# STM32_MPU_IOs.net
KiCad netlist of a schematic drawn in Altium Designer
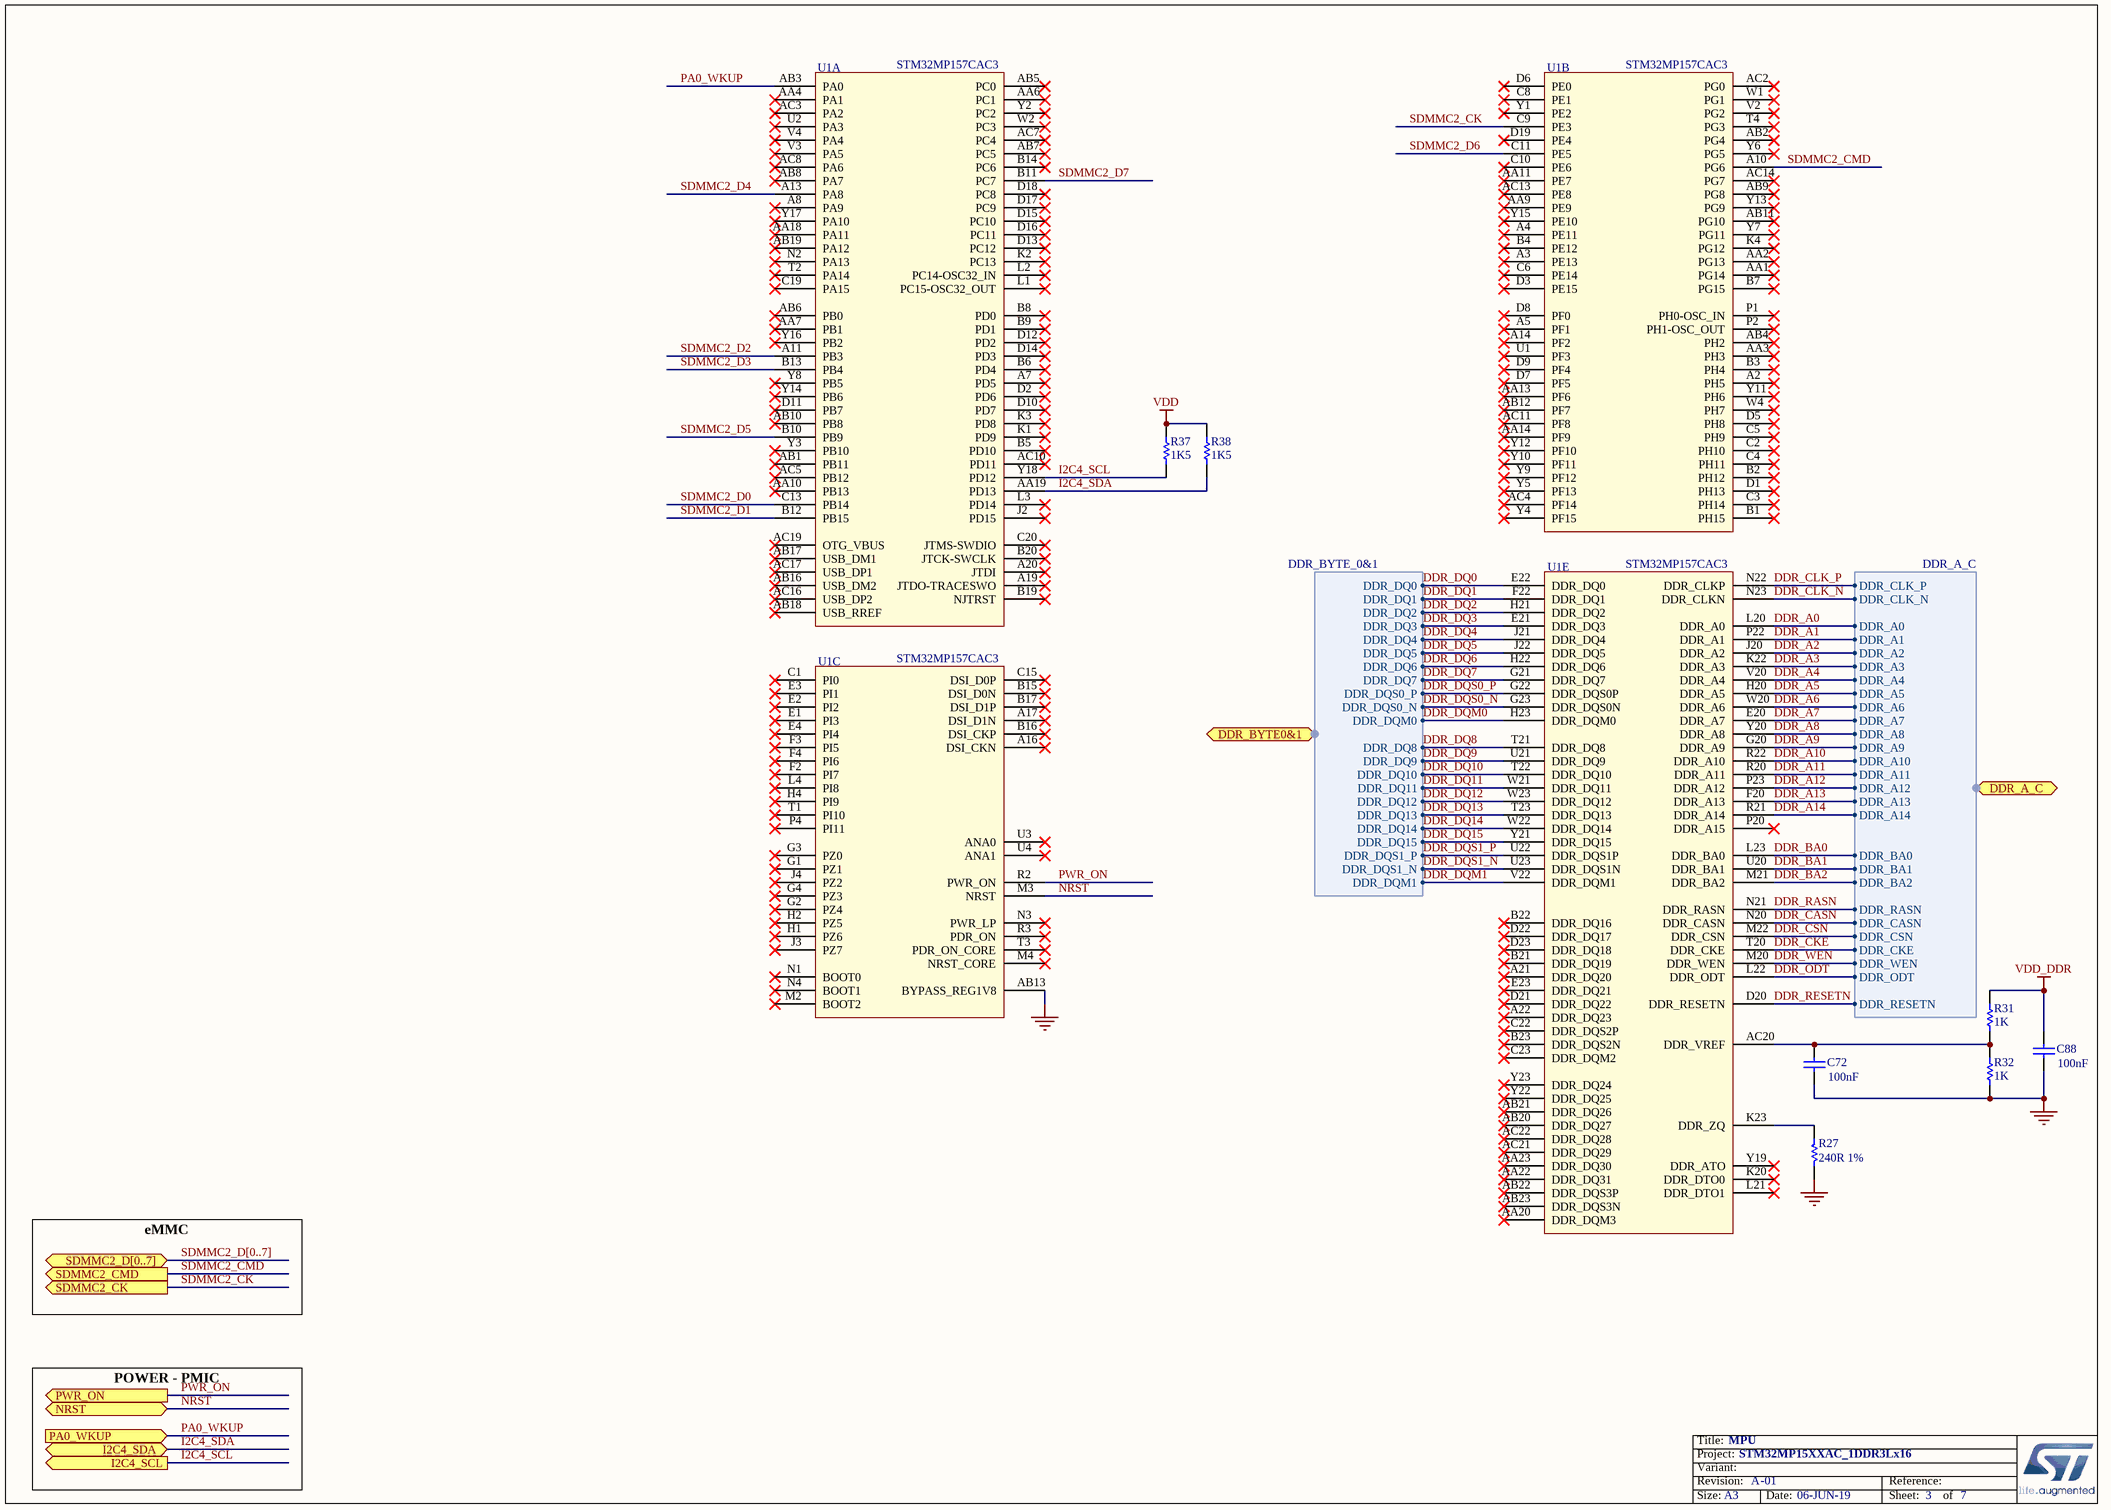
[diagram p0: STM32_MPU_IOs.SchDoc]

(export (version "E")
  (design (tool "Eeschema 10.0.6"))
  (components
    (comp (ref "C72")
      (value "100nF")
      (footprint "C0402")
      (description "Capacitor, MLCC, 100nF, 16V, X7R, 10%, 0402, T=0.5mm")
      (fields
        (field (name "INTERNAL_PART_NUMBER") "MCD-00006")
        (field (name "MANUFACTURER_PART_NUMBER") "CC0402KRX7R7BB104")
        (field (name "PROVIDED_BY") "SUBCO")
      )
      (libsource (lib "MCD_PARTS_database") (part "Capacitor"))
    )
    (comp (ref "C88")
      (value "100nF")
      (footprint "C0402")
      (description "Capacitor, MLCC, 100nF, 16V, X7R, 10%, 0402, T=0.5mm")
      (fields
        (field (name "INTERNAL_PART_NUMBER") "MCD-00006")
        (field (name "MANUFACTURER_PART_NUMBER") "CC0402KRX7R7BB104")
        (field (name "PROVIDED_BY") "SUBCO")
      )
      (libsource (lib "MCD_PARTS_database") (part "Capacitor"))
    )
    (comp (ref "R27")
      (value "240R 1%")
      (footprint "R0402")
      (description "Resistor,240R,0402,1%,1/16W")
      (fields
        (field (name "INTERNAL_PART_NUMBER") "MCD-00120")
        (field (name "MANUFACTURER_PART_NUMBER") "RC0402FR-07240RL")
        (field (name "PROVIDED_BY") "SUBCO")
      )
      (libsource (lib "MCD_PARTS_database") (part "Resistor"))
    )
    (comp (ref "R31")
      (value "1K")
      (footprint "R0402")
      (description "Resistor,1K,0402,1%,1/16W")
      (fields
        (field (name "INTERNAL_PART_NUMBER") "MCD-00061")
        (field (name "MANUFACTURER_PART_NUMBER") "RC0402FR-071KL")
        (field (name "PROVIDED_BY") "SUBCO")
      )
      (libsource (lib "MCD_PARTS_database") (part "Resistor"))
    )
    (comp (ref "R32")
      (value "1K")
      (footprint "R0402")
      (description "Resistor,1K,0402,1%,1/16W")
      (fields
        (field (name "INTERNAL_PART_NUMBER") "MCD-00061")
        (field (name "MANUFACTURER_PART_NUMBER") "RC0402FR-071KL")
        (field (name "PROVIDED_BY") "SUBCO")
      )
      (libsource (lib "MCD_PARTS_database") (part "Resistor"))
    )
    (comp (ref "R37")
      (value "1K5")
      (footprint "R0402")
      (description "Resistor,1K5,0402,1%,1/16W")
      (fields
        (field (name "INTERNAL_PART_NUMBER") "MCD-00068")
        (field (name "MANUFACTURER_PART_NUMBER") "RC0402FR-071K5L")
        (field (name "PROVIDED_BY") "SUBCO")
      )
      (libsource (lib "MCD_PARTS_database") (part "Resistor"))
    )
    (comp (ref "R38")
      (value "1K5")
      (footprint "R0402")
      (description "Resistor,1K5,0402,1%,1/16W")
      (fields
        (field (name "INTERNAL_PART_NUMBER") "MCD-00068")
        (field (name "MANUFACTURER_PART_NUMBER") "RC0402FR-071K5L")
        (field (name "PROVIDED_BY") "SUBCO")
      )
      (libsource (lib "MCD_PARTS_database") (part "Resistor"))
    )
    (comp (ref "U1")
      (value "STM32MP157CAC3")
      (footprint "ICC_TFBGA361_12X12_STM32MP157CAC3_P050-065")
      (description "MPU TFBGA12x12 secure boot+crypto")
      (fields
        (field (name "INTERNAL_PART_NUMBER") "MCD-00677")
        (field (name "MANUFACTURER") "STMICROELECTRONICS")
        (field (name "PROVIDED_BY") "SUBCO with ST control")
      )
      (libsource (lib "MCD_PARTS_database") (part "STM32MP157CAC3"))
    )
  )
  (nets
    (net (code "3") (name "/DDR_A0") (class "Default")
      (node (ref "U1") (pin "L20") (pinfunction "DDR_A0_L20") (pintype "passive"))
    )
    (net (code "4") (name "/DDR_A1") (class "Default")
      (node (ref "U1") (pin "P22") (pinfunction "DDR_A1_P22") (pintype "passive"))
    )
    (net (code "5") (name "/DDR_A2") (class "Default")
      (node (ref "U1") (pin "J20") (pinfunction "DDR_A2_J20") (pintype "passive"))
    )
    (net (code "6") (name "/DDR_A3") (class "Default")
      (node (ref "U1") (pin "K22") (pinfunction "DDR_A3_K22") (pintype "passive"))
    )
    (net (code "7") (name "/DDR_A4") (class "Default")
      (node (ref "U1") (pin "V20") (pinfunction "DDR_A4_V20") (pintype "passive"))
    )
    (net (code "8") (name "/DDR_A5") (class "Default")
      (node (ref "U1") (pin "H20") (pinfunction "DDR_A5_H20") (pintype "passive"))
    )
    (net (code "9") (name "/DDR_A6") (class "Default")
      (node (ref "U1") (pin "W20") (pinfunction "DDR_A6_W20") (pintype "passive"))
    )
    (net (code "10") (name "/DDR_A7") (class "Default")
      (node (ref "U1") (pin "E20") (pinfunction "DDR_A7_E20") (pintype "passive"))
    )
    (net (code "11") (name "/DDR_A8") (class "Default")
      (node (ref "U1") (pin "Y20") (pinfunction "DDR_A8_Y20") (pintype "passive"))
    )
    (net (code "12") (name "/DDR_A9") (class "Default")
      (node (ref "U1") (pin "G20") (pinfunction "DDR_A9_G20") (pintype "passive"))
    )
    (net (code "13") (name "/DDR_A10") (class "Default")
      (node (ref "U1") (pin "R22") (pinfunction "DDR_A10_R22") (pintype "passive"))
    )
    (net (code "14") (name "/DDR_A11") (class "Default")
      (node (ref "U1") (pin "R20") (pinfunction "DDR_A11_R20") (pintype "passive"))
    )
    (net (code "15") (name "/DDR_A12") (class "Default")
      (node (ref "U1") (pin "P23") (pinfunction "DDR_A12_P23") (pintype "passive"))
    )
    (net (code "16") (name "/DDR_A13") (class "Default")
      (node (ref "U1") (pin "F20") (pinfunction "DDR_A13_F20") (pintype "passive"))
    )
    (net (code "17") (name "/DDR_A14") (class "Default")
      (node (ref "U1") (pin "R21") (pinfunction "DDR_A14_R21") (pintype "passive"))
    )
    (net (code "18") (name "/DDR_BA0") (class "Default")
      (node (ref "U1") (pin "L23") (pinfunction "DDR_BA0_L23") (pintype "passive"))
    )
    (net (code "19") (name "/DDR_BA1") (class "Default")
      (node (ref "U1") (pin "U20") (pinfunction "DDR_BA1_U20") (pintype "passive"))
    )
    (net (code "20") (name "/DDR_BA2") (class "Default")
      (node (ref "U1") (pin "M21") (pinfunction "DDR_BA2_M21") (pintype "passive"))
    )
    (net (code "21") (name "/DDR_CASN") (class "Default")
      (node (ref "U1") (pin "N20") (pinfunction "DDR_CASN_N20") (pintype "passive"))
    )
    (net (code "22") (name "/DDR_CKE") (class "Default")
      (node (ref "U1") (pin "T20") (pinfunction "DDR_CKE_T20") (pintype "passive"))
    )
    (net (code "23") (name "/DDR_CLK_N") (class "Default")
      (node (ref "U1") (pin "N23") (pinfunction "DDR_CLKN_N23") (pintype "passive"))
    )
    (net (code "24") (name "/DDR_CLK_P") (class "Default")
      (node (ref "U1") (pin "N22") (pinfunction "DDR_CLKP_N22") (pintype "passive"))
    )
    (net (code "25") (name "/DDR_CSN") (class "Default")
      (node (ref "U1") (pin "M22") (pinfunction "DDR_CSN_M22") (pintype "passive"))
    )
    (net (code "26") (name "/DDR_DQ0") (class "Default")
      (node (ref "U1") (pin "E22") (pinfunction "DDR_DQ0_E22") (pintype "passive"))
    )
    (net (code "27") (name "/DDR_DQ1") (class "Default")
      (node (ref "U1") (pin "F22") (pinfunction "DDR_DQ1_F22") (pintype "passive"))
    )
    (net (code "28") (name "/DDR_DQ2") (class "Default")
      (node (ref "U1") (pin "H21") (pinfunction "DDR_DQ2_H21") (pintype "passive"))
    )
    (net (code "29") (name "/DDR_DQ3") (class "Default")
      (node (ref "U1") (pin "E21") (pinfunction "DDR_DQ3_E21") (pintype "passive"))
    )
    (net (code "30") (name "/DDR_DQ4") (class "Default")
      (node (ref "U1") (pin "J21") (pinfunction "DDR_DQ4_J21") (pintype "passive"))
    )
    (net (code "31") (name "/DDR_DQ5") (class "Default")
      (node (ref "U1") (pin "J22") (pinfunction "DDR_DQ5_J22") (pintype "passive"))
    )
    (net (code "32") (name "/DDR_DQ6") (class "Default")
      (node (ref "U1") (pin "H22") (pinfunction "DDR_DQ6_H22") (pintype "passive"))
    )
    (net (code "33") (name "/DDR_DQ7") (class "Default")
      (node (ref "U1") (pin "G21") (pinfunction "DDR_DQ7_G21") (pintype "passive"))
    )
    (net (code "34") (name "/DDR_DQ8") (class "Default")
      (node (ref "U1") (pin "T21") (pinfunction "DDR_DQ8_T21") (pintype "passive"))
    )
    (net (code "35") (name "/DDR_DQ9") (class "Default")
      (node (ref "U1") (pin "U21") (pinfunction "DDR_DQ9_U21") (pintype "passive"))
    )
    (net (code "36") (name "/DDR_DQ10") (class "Default")
      (node (ref "U1") (pin "T22") (pinfunction "DDR_DQ10_T22") (pintype "passive"))
    )
    (net (code "37") (name "/DDR_DQ11") (class "Default")
      (node (ref "U1") (pin "W21") (pinfunction "DDR_DQ11_W21") (pintype "passive"))
    )
    (net (code "38") (name "/DDR_DQ12") (class "Default")
      (node (ref "U1") (pin "W23") (pinfunction "DDR_DQ12_W23") (pintype "passive"))
    )
    (net (code "39") (name "/DDR_DQ13") (class "Default")
      (node (ref "U1") (pin "T23") (pinfunction "DDR_DQ13_T23") (pintype "passive"))
    )
    (net (code "40") (name "/DDR_DQ14") (class "Default")
      (node (ref "U1") (pin "W22") (pinfunction "DDR_DQ14_W22") (pintype "passive"))
    )
    (net (code "41") (name "/DDR_DQ15") (class "Default")
      (node (ref "U1") (pin "Y21") (pinfunction "DDR_DQ15_Y21") (pintype "passive"))
    )
    (net (code "42") (name "/DDR_DQM0") (class "Default")
      (node (ref "U1") (pin "H23") (pinfunction "DDR_DQM0_H23") (pintype "passive"))
    )
    (net (code "43") (name "/DDR_DQM1") (class "Default")
      (node (ref "U1") (pin "V22") (pinfunction "DDR_DQM1_V22") (pintype "passive"))
    )
    (net (code "44") (name "/DDR_DQS0_N") (class "Default")
      (node (ref "U1") (pin "G23") (pinfunction "DDR_DQS0N_G23") (pintype "passive"))
    )
    (net (code "45") (name "/DDR_DQS0_P") (class "Default")
      (node (ref "U1") (pin "G22") (pinfunction "DDR_DQS0P_G22") (pintype "passive"))
    )
    (net (code "46") (name "/DDR_DQS1_N") (class "Default")
      (node (ref "U1") (pin "U23") (pinfunction "DDR_DQS1N_U23") (pintype "passive"))
    )
    (net (code "47") (name "/DDR_DQS1_P") (class "Default")
      (node (ref "U1") (pin "U22") (pinfunction "DDR_DQS1P_U22") (pintype "passive"))
    )
    (net (code "48") (name "/DDR_ODT") (class "Default")
      (node (ref "U1") (pin "L22") (pinfunction "DDR_ODT_L22") (pintype "passive"))
    )
    (net (code "49") (name "/DDR_RASN") (class "Default")
      (node (ref "U1") (pin "N21") (pinfunction "DDR_RASN_N21") (pintype "passive"))
    )
    (net (code "50") (name "/DDR_RESETN") (class "Default")
      (node (ref "U1") (pin "D20") (pinfunction "DDR_RESETN_D20") (pintype "passive"))
    )
    (net (code "51") (name "/DDR_WEN") (class "Default")
      (node (ref "U1") (pin "M20") (pinfunction "DDR_WEN_M20") (pintype "passive"))
    )
    (net (code "52") (name "/I2C4_SCL") (class "Default")
      (node (ref "R37") (pin "2") (pinfunction "2_2") (pintype "passive"))
      (node (ref "U1") (pin "Y18") (pinfunction "PD12_Y18") (pintype "passive"))
    )
    (net (code "53") (name "/I2C4_SDA") (class "Default")
      (node (ref "R38") (pin "2") (pinfunction "2_2") (pintype "passive"))
      (node (ref "U1") (pin "AA19") (pinfunction "PD13_AA19") (pintype "passive"))
    )
    (net (code "54") (name "/NRST") (class "Default")
      (node (ref "U1") (pin "M3") (pinfunction "NRST_M3") (pintype "passive"))
    )
    (net (code "55") (name "/PA0_WKUP") (class "Default")
      (node (ref "U1") (pin "AB3") (pinfunction "PA0_AB3") (pintype "passive"))
    )
    (net (code "56") (name "/PWR_ON") (class "Default")
      (node (ref "U1") (pin "R2") (pinfunction "PWR_ON_R2") (pintype "passive"))
    )
    (net (code "57") (name "/SDMMC2_CK") (class "Default")
      (node (ref "U1") (pin "C9") (pinfunction "PE3_C9") (pintype "passive"))
    )
    (net (code "58") (name "/SDMMC2_CMD") (class "Default")
      (node (ref "U1") (pin "A10") (pinfunction "PG6_A10") (pintype "passive"))
    )
    (net (code "59") (name "/SDMMC2_D0") (class "Default")
      (node (ref "U1") (pin "C13") (pinfunction "PB14_C13") (pintype "passive"))
    )
    (net (code "60") (name "/SDMMC2_D1") (class "Default")
      (node (ref "U1") (pin "B12") (pinfunction "PB15_B12") (pintype "passive"))
    )
    (net (code "61") (name "/SDMMC2_D2") (class "Default")
      (node (ref "U1") (pin "A11") (pinfunction "PB3_A11") (pintype "passive"))
    )
    (net (code "62") (name "/SDMMC2_D3") (class "Default")
      (node (ref "U1") (pin "B13") (pinfunction "PB4_B13") (pintype "passive"))
    )
    (net (code "63") (name "/SDMMC2_D4") (class "Default")
      (node (ref "U1") (pin "A13") (pinfunction "PA8_A13") (pintype "passive"))
    )
    (net (code "64") (name "/SDMMC2_D5") (class "Default")
      (node (ref "U1") (pin "B10") (pinfunction "PB9_B10") (pintype "passive"))
    )
    (net (code "65") (name "/SDMMC2_D6") (class "Default")
      (node (ref "U1") (pin "C11") (pinfunction "PE5_C11") (pintype "passive"))
    )
    (net (code "66") (name "/SDMMC2_D7") (class "Default")
      (node (ref "U1") (pin "B11") (pinfunction "PC7_B11") (pintype "passive"))
    )
    (net (code "70") (name "GND") (class "Default")
      (node (ref "C72") (pin "1") (pinfunction "1_1") (pintype "passive"))
      (node (ref "C88") (pin "1") (pinfunction "1_1") (pintype "passive"))
      (node (ref "R27") (pin "2") (pinfunction "2_2") (pintype "passive"))
      (node (ref "R32") (pin "1") (pinfunction "1_1") (pintype "passive"))
      (node (ref "U1") (pin "AB13") (pinfunction "BYPASS_REG1V8_AB13") (pintype "passive"))
    )
    (net (code "71") (name "Net-(U1E-DDR_VREF)") (class "Default")
      (node (ref "C72") (pin "2") (pinfunction "2_2") (pintype "passive"))
      (node (ref "R31") (pin "1") (pinfunction "1_1") (pintype "passive"))
      (node (ref "R32") (pin "2") (pinfunction "2_2") (pintype "passive"))
      (node (ref "U1") (pin "AC20") (pinfunction "DDR_VREF_AC20") (pintype "passive"))
    )
    (net (code "72") (name "Net-(U1E-DDR_ZQ)") (class "Default")
      (node (ref "R27") (pin "1") (pinfunction "1_1") (pintype "passive"))
      (node (ref "U1") (pin "K23") (pinfunction "DDR_ZQ_K23") (pintype "passive"))
    )
    (net (code "73") (name "VDD") (class "Default")
      (node (ref "R37") (pin "1") (pinfunction "1_1") (pintype "passive"))
      (node (ref "R38") (pin "1") (pinfunction "1_1") (pintype "passive"))
    )
    (net (code "74") (name "VDD_DDR") (class "Default")
      (node (ref "C88") (pin "2") (pinfunction "2_2") (pintype "passive"))
      (node (ref "R31") (pin "2") (pinfunction "2_2") (pintype "passive"))
    )
    (net (code "75") (name "unconnected-(U1A-JTCK-SWCLK-PadB20)") (class "Default")
      (node (ref "U1") (pin "B20") (pinfunction "JTCK-SWCLK_B20") (pintype "passive+no_connect"))
    )
    (net (code "76") (name "unconnected-(U1A-JTDI-PadA20)") (class "Default")
      (node (ref "U1") (pin "A20") (pinfunction "JTDI_A20") (pintype "passive+no_connect"))
    )
    (net (code "77") (name "unconnected-(U1A-JTDO-TRACESWO-PadA19)") (class "Default")
      (node (ref "U1") (pin "A19") (pinfunction "JTDO-TRACESWO_A19") (pintype "passive+no_connect"))
    )
    (net (code "78") (name "unconnected-(U1A-JTMS-SWDIO-PadC20)") (class "Default")
      (node (ref "U1") (pin "C20") (pinfunction "JTMS-SWDIO_C20") (pintype "passive+no_connect"))
    )
    (net (code "79") (name "unconnected-(U1A-NJTRST-PadB19)") (class "Default")
      (node (ref "U1") (pin "B19") (pinfunction "NJTRST_B19") (pintype "passive+no_connect"))
    )
    (net (code "80") (name "unconnected-(U1A-OTG_VBUS-PadAC19)") (class "Default")
      (node (ref "U1") (pin "AC19") (pinfunction "OTG_VBUS_AC19") (pintype "passive+no_connect"))
    )
    (net (code "81") (name "unconnected-(U1A-PA1-PadAA4)") (class "Default")
      (node (ref "U1") (pin "AA4") (pinfunction "PA1_AA4") (pintype "passive+no_connect"))
    )
    (net (code "82") (name "unconnected-(U1A-PA2-PadAC3)") (class "Default")
      (node (ref "U1") (pin "AC3") (pinfunction "PA2_AC3") (pintype "passive+no_connect"))
    )
    (net (code "83") (name "unconnected-(U1A-PA3-PadU2)") (class "Default")
      (node (ref "U1") (pin "U2") (pinfunction "PA3_U2") (pintype "passive+no_connect"))
    )
    (net (code "84") (name "unconnected-(U1A-PA4-PadV4)") (class "Default")
      (node (ref "U1") (pin "V4") (pinfunction "PA4_V4") (pintype "passive+no_connect"))
    )
    (net (code "85") (name "unconnected-(U1A-PA5-PadV3)") (class "Default")
      (node (ref "U1") (pin "V3") (pinfunction "PA5_V3") (pintype "passive+no_connect"))
    )
    (net (code "86") (name "unconnected-(U1A-PA6-PadAC8)") (class "Default")
      (node (ref "U1") (pin "AC8") (pinfunction "PA6_AC8") (pintype "passive+no_connect"))
    )
    (net (code "87") (name "unconnected-(U1A-PA7-PadAB8)") (class "Default")
      (node (ref "U1") (pin "AB8") (pinfunction "PA7_AB8") (pintype "passive+no_connect"))
    )
    (net (code "88") (name "unconnected-(U1A-PA9-PadA8)") (class "Default")
      (node (ref "U1") (pin "A8") (pinfunction "PA9_A8") (pintype "passive+no_connect"))
    )
    (net (code "89") (name "unconnected-(U1A-PA10-PadY17)") (class "Default")
      (node (ref "U1") (pin "Y17") (pinfunction "PA10_Y17") (pintype "passive+no_connect"))
    )
    (net (code "90") (name "unconnected-(U1A-PA11-PadAA18)") (class "Default")
      (node (ref "U1") (pin "AA18") (pinfunction "PA11_AA18") (pintype "passive+no_connect"))
    )
    (net (code "91") (name "unconnected-(U1A-PA12-PadAB19)") (class "Default")
      (node (ref "U1") (pin "AB19") (pinfunction "PA12_AB19") (pintype "passive+no_connect"))
    )
    (net (code "92") (name "unconnected-(U1A-PA13-PadN2)") (class "Default")
      (node (ref "U1") (pin "N2") (pinfunction "PA13_N2") (pintype "passive+no_connect"))
    )
    (net (code "93") (name "unconnected-(U1A-PA14-PadT2)") (class "Default")
      (node (ref "U1") (pin "T2") (pinfunction "PA14_T2") (pintype "passive+no_connect"))
    )
    (net (code "94") (name "unconnected-(U1A-PA15-PadC19)") (class "Default")
      (node (ref "U1") (pin "C19") (pinfunction "PA15_C19") (pintype "passive+no_connect"))
    )
    (net (code "95") (name "unconnected-(U1A-PB0-PadAB6)") (class "Default")
      (node (ref "U1") (pin "AB6") (pinfunction "PB0_AB6") (pintype "passive+no_connect"))
    )
    (net (code "96") (name "unconnected-(U1A-PB1-PadAA7)") (class "Default")
      (node (ref "U1") (pin "AA7") (pinfunction "PB1_AA7") (pintype "passive+no_connect"))
    )
    (net (code "97") (name "unconnected-(U1A-PB2-PadY16)") (class "Default")
      (node (ref "U1") (pin "Y16") (pinfunction "PB2_Y16") (pintype "passive+no_connect"))
    )
    (net (code "98") (name "unconnected-(U1A-PB5-PadY8)") (class "Default")
      (node (ref "U1") (pin "Y8") (pinfunction "PB5_Y8") (pintype "passive+no_connect"))
    )
    (net (code "99") (name "unconnected-(U1A-PB6-PadY14)") (class "Default")
      (node (ref "U1") (pin "Y14") (pinfunction "PB6_Y14") (pintype "passive+no_connect"))
    )
    (net (code "100") (name "unconnected-(U1A-PB7-PadD11)") (class "Default")
      (node (ref "U1") (pin "D11") (pinfunction "PB7_D11") (pintype "passive+no_connect"))
    )
    (net (code "101") (name "unconnected-(U1A-PB8-PadAB10)") (class "Default")
      (node (ref "U1") (pin "AB10") (pinfunction "PB8_AB10") (pintype "passive+no_connect"))
    )
    (net (code "102") (name "unconnected-(U1A-PB10-PadY3)") (class "Default")
      (node (ref "U1") (pin "Y3") (pinfunction "PB10_Y3") (pintype "passive+no_connect"))
    )
    (net (code "103") (name "unconnected-(U1A-PB11-PadAB1)") (class "Default")
      (node (ref "U1") (pin "AB1") (pinfunction "PB11_AB1") (pintype "passive+no_connect"))
    )
    (net (code "104") (name "unconnected-(U1A-PB12-PadAC5)") (class "Default")
      (node (ref "U1") (pin "AC5") (pinfunction "PB12_AC5") (pintype "passive+no_connect"))
    )
    (net (code "105") (name "unconnected-(U1A-PB13-PadAA10)") (class "Default")
      (node (ref "U1") (pin "AA10") (pinfunction "PB13_AA10") (pintype "passive+no_connect"))
    )
    (net (code "106") (name "unconnected-(U1A-PC0-PadAB5)") (class "Default")
      (node (ref "U1") (pin "AB5") (pinfunction "PC0_AB5") (pintype "passive+no_connect"))
    )
    (net (code "107") (name "unconnected-(U1A-PC1-PadAA6)") (class "Default")
      (node (ref "U1") (pin "AA6") (pinfunction "PC1_AA6") (pintype "passive+no_connect"))
    )
    (net (code "108") (name "unconnected-(U1A-PC2-PadY2)") (class "Default")
      (node (ref "U1") (pin "Y2") (pinfunction "PC2_Y2") (pintype "passive+no_connect"))
    )
    (net (code "109") (name "unconnected-(U1A-PC3-PadW2)") (class "Default")
      (node (ref "U1") (pin "W2") (pinfunction "PC3_W2") (pintype "passive+no_connect"))
    )
    (net (code "110") (name "unconnected-(U1A-PC4-PadAC7)") (class "Default")
      (node (ref "U1") (pin "AC7") (pinfunction "PC4_AC7") (pintype "passive+no_connect"))
    )
    (net (code "111") (name "unconnected-(U1A-PC5-PadAB7)") (class "Default")
      (node (ref "U1") (pin "AB7") (pinfunction "PC5_AB7") (pintype "passive+no_connect"))
    )
    (net (code "112") (name "unconnected-(U1A-PC6-PadB14)") (class "Default")
      (node (ref "U1") (pin "B14") (pinfunction "PC6_B14") (pintype "passive+no_connect"))
    )
    (net (code "113") (name "unconnected-(U1A-PC8-PadD18)") (class "Default")
      (node (ref "U1") (pin "D18") (pinfunction "PC8_D18") (pintype "passive+no_connect"))
    )
    (net (code "114") (name "unconnected-(U1A-PC9-PadD17)") (class "Default")
      (node (ref "U1") (pin "D17") (pinfunction "PC9_D17") (pintype "passive+no_connect"))
    )
    (net (code "115") (name "unconnected-(U1A-PC10-PadD15)") (class "Default")
      (node (ref "U1") (pin "D15") (pinfunction "PC10_D15") (pintype "passive+no_connect"))
    )
    (net (code "116") (name "unconnected-(U1A-PC11-PadD16)") (class "Default")
      (node (ref "U1") (pin "D16") (pinfunction "PC11_D16") (pintype "passive+no_connect"))
    )
    (net (code "117") (name "unconnected-(U1A-PC12-PadD13)") (class "Default")
      (node (ref "U1") (pin "D13") (pinfunction "PC12_D13") (pintype "passive+no_connect"))
    )
    (net (code "118") (name "unconnected-(U1A-PC13-PadK2)") (class "Default")
      (node (ref "U1") (pin "K2") (pinfunction "PC13_K2") (pintype "passive+no_connect"))
    )
    (net (code "119") (name "unconnected-(U1A-PC14-OSC32_IN-PadL2)") (class "Default")
      (node (ref "U1") (pin "L2") (pinfunction "PC14-OSC32_IN_L2") (pintype "passive+no_connect"))
    )
    (net (code "120") (name "unconnected-(U1A-PC15-OSC32_OUT-PadL1)") (class "Default")
      (node (ref "U1") (pin "L1") (pinfunction "PC15-OSC32_OUT_L1") (pintype "passive+no_connect"))
    )
    (net (code "121") (name "unconnected-(U1A-PD0-PadB8)") (class "Default")
      (node (ref "U1") (pin "B8") (pinfunction "PD0_B8") (pintype "passive+no_connect"))
    )
    (net (code "122") (name "unconnected-(U1A-PD1-PadB9)") (class "Default")
      (node (ref "U1") (pin "B9") (pinfunction "PD1_B9") (pintype "passive+no_connect"))
    )
    (net (code "123") (name "unconnected-(U1A-PD2-PadD12)") (class "Default")
      (node (ref "U1") (pin "D12") (pinfunction "PD2_D12") (pintype "passive+no_connect"))
    )
    (net (code "124") (name "unconnected-(U1A-PD3-PadD14)") (class "Default")
      (node (ref "U1") (pin "D14") (pinfunction "PD3_D14") (pintype "passive+no_connect"))
    )
    (net (code "125") (name "unconnected-(U1A-PD4-PadB6)") (class "Default")
      (node (ref "U1") (pin "B6") (pinfunction "PD4_B6") (pintype "passive+no_connect"))
    )
    (net (code "126") (name "unconnected-(U1A-PD5-PadA7)") (class "Default")
      (node (ref "U1") (pin "A7") (pinfunction "PD5_A7") (pintype "passive+no_connect"))
    )
    (net (code "127") (name "unconnected-(U1A-PD6-PadD2)") (class "Default")
      (node (ref "U1") (pin "D2") (pinfunction "PD6_D2") (pintype "passive+no_connect"))
    )
    (net (code "128") (name "unconnected-(U1A-PD7-PadD10)") (class "Default")
      (node (ref "U1") (pin "D10") (pinfunction "PD7_D10") (pintype "passive+no_connect"))
    )
    (net (code "129") (name "unconnected-(U1A-PD8-PadK3)") (class "Default")
      (node (ref "U1") (pin "K3") (pinfunction "PD8_K3") (pintype "passive+no_connect"))
    )
    (net (code "130") (name "unconnected-(U1A-PD9-PadK1)") (class "Default")
      (node (ref "U1") (pin "K1") (pinfunction "PD9_K1") (pintype "passive+no_connect"))
    )
    (net (code "131") (name "unconnected-(U1A-PD10-PadB5)") (class "Default")
      (node (ref "U1") (pin "B5") (pinfunction "PD10_B5") (pintype "passive+no_connect"))
    )
    (net (code "132") (name "unconnected-(U1A-PD11-PadAC10)") (class "Default")
      (node (ref "U1") (pin "AC10") (pinfunction "PD11_AC10") (pintype "passive+no_connect"))
    )
    (net (code "133") (name "unconnected-(U1A-PD14-PadL3)") (class "Default")
      (node (ref "U1") (pin "L3") (pinfunction "PD14_L3") (pintype "passive+no_connect"))
    )
    (net (code "134") (name "unconnected-(U1A-PD15-PadJ2)") (class "Default")
      (node (ref "U1") (pin "J2") (pinfunction "PD15_J2") (pintype "passive+no_connect"))
    )
    (net (code "135") (name "unconnected-(U1A-USB_DM1-PadAB17)") (class "Default")
      (node (ref "U1") (pin "AB17") (pinfunction "USB_DM1_AB17") (pintype "passive+no_connect"))
    )
    (net (code "136") (name "unconnected-(U1A-USB_DM2-PadAB16)") (class "Default")
      (node (ref "U1") (pin "AB16") (pinfunction "USB_DM2_AB16") (pintype "passive+no_connect"))
    )
    (net (code "137") (name "unconnected-(U1A-USB_DP1-PadAC17)") (class "Default")
      (node (ref "U1") (pin "AC17") (pinfunction "USB_DP1_AC17") (pintype "passive+no_connect"))
    )
    (net (code "138") (name "unconnected-(U1A-USB_DP2-PadAC16)") (class "Default")
      (node (ref "U1") (pin "AC16") (pinfunction "USB_DP2_AC16") (pintype "passive+no_connect"))
    )
    (net (code "139") (name "unconnected-(U1A-USB_RREF-PadAB18)") (class "Default")
      (node (ref "U1") (pin "AB18") (pinfunction "USB_RREF_AB18") (pintype "passive+no_connect"))
    )
    (net (code "140") (name "unconnected-(U1B-PE0-PadD6)") (class "Default")
      (node (ref "U1") (pin "D6") (pinfunction "PE0_D6") (pintype "passive+no_connect"))
    )
    (net (code "141") (name "unconnected-(U1B-PE1-PadC8)") (class "Default")
      (node (ref "U1") (pin "C8") (pinfunction "PE1_C8") (pintype "passive+no_connect"))
    )
    (net (code "142") (name "unconnected-(U1B-PE2-PadY1)") (class "Default")
      (node (ref "U1") (pin "Y1") (pinfunction "PE2_Y1") (pintype "passive+no_connect"))
    )
    (net (code "143") (name "unconnected-(U1B-PE4-PadD19)") (class "Default")
      (node (ref "U1") (pin "D19") (pinfunction "PE4_D19") (pintype "passive+no_connect"))
    )
    (net (code "144") (name "unconnected-(U1B-PE6-PadC10)") (class "Default")
      (node (ref "U1") (pin "C10") (pinfunction "PE6_C10") (pintype "passive+no_connect"))
    )
    (net (code "145") (name "unconnected-(U1B-PE7-PadAA11)") (class "Default")
      (node (ref "U1") (pin "AA11") (pinfunction "PE7_AA11") (pintype "passive+no_connect"))
    )
    (net (code "146") (name "unconnected-(U1B-PE8-PadAC13)") (class "Default")
      (node (ref "U1") (pin "AC13") (pinfunction "PE8_AC13") (pintype "passive+no_connect"))
    )
    (net (code "147") (name "unconnected-(U1B-PE9-PadAA9)") (class "Default")
      (node (ref "U1") (pin "AA9") (pinfunction "PE9_AA9") (pintype "passive+no_connect"))
    )
    (net (code "148") (name "unconnected-(U1B-PE10-PadY15)") (class "Default")
      (node (ref "U1") (pin "Y15") (pinfunction "PE10_Y15") (pintype "passive+no_connect"))
    )
    (net (code "149") (name "unconnected-(U1B-PE11-PadA4)") (class "Default")
      (node (ref "U1") (pin "A4") (pinfunction "PE11_A4") (pintype "passive+no_connect"))
    )
    (net (code "150") (name "unconnected-(U1B-PE12-PadB4)") (class "Default")
      (node (ref "U1") (pin "B4") (pinfunction "PE12_B4") (pintype "passive+no_connect"))
    )
    (net (code "151") (name "unconnected-(U1B-PE13-PadA3)") (class "Default")
      (node (ref "U1") (pin "A3") (pinfunction "PE13_A3") (pintype "passive+no_connect"))
    )
    (net (code "152") (name "unconnected-(U1B-PE14-PadC6)") (class "Default")
      (node (ref "U1") (pin "C6") (pinfunction "PE14_C6") (pintype "passive+no_connect"))
    )
    (net (code "153") (name "unconnected-(U1B-PE15-PadD3)") (class "Default")
      (node (ref "U1") (pin "D3") (pinfunction "PE15_D3") (pintype "passive+no_connect"))
    )
    (net (code "154") (name "unconnected-(U1B-PF0-PadD8)") (class "Default")
      (node (ref "U1") (pin "D8") (pinfunction "PF0_D8") (pintype "passive+no_connect"))
    )
    (net (code "155") (name "unconnected-(U1B-PF1-PadA5)") (class "Default")
      (node (ref "U1") (pin "A5") (pinfunction "PF1_A5") (pintype "passive+no_connect"))
    )
    (net (code "156") (name "unconnected-(U1B-PF2-PadA14)") (class "Default")
      (node (ref "U1") (pin "A14") (pinfunction "PF2_A14") (pintype "passive+no_connect"))
    )
    (net (code "157") (name "unconnected-(U1B-PF3-PadU1)") (class "Default")
      (node (ref "U1") (pin "U1") (pinfunction "PF3_U1") (pintype "passive+no_connect"))
    )
    (net (code "158") (name "unconnected-(U1B-PF4-PadD9)") (class "Default")
      (node (ref "U1") (pin "D9") (pinfunction "PF4_D9") (pintype "passive+no_connect"))
    )
    (net (code "159") (name "unconnected-(U1B-PF5-PadD7)") (class "Default")
      (node (ref "U1") (pin "D7") (pinfunction "PF5_D7") (pintype "passive+no_connect"))
    )
    (net (code "160") (name "unconnected-(U1B-PF6-PadAA13)") (class "Default")
      (node (ref "U1") (pin "AA13") (pinfunction "PF6_AA13") (pintype "passive+no_connect"))
    )
    (net (code "161") (name "unconnected-(U1B-PF7-PadAB12)") (class "Default")
      (node (ref "U1") (pin "AB12") (pinfunction "PF7_AB12") (pintype "passive+no_connect"))
    )
    (net (code "162") (name "unconnected-(U1B-PF8-PadAC11)") (class "Default")
      (node (ref "U1") (pin "AC11") (pinfunction "PF8_AC11") (pintype "passive+no_connect"))
    )
    (net (code "163") (name "unconnected-(U1B-PF9-PadAA14)") (class "Default")
      (node (ref "U1") (pin "AA14") (pinfunction "PF9_AA14") (pintype "passive+no_connect"))
    )
    (net (code "164") (name "unconnected-(U1B-PF10-PadY12)") (class "Default")
      (node (ref "U1") (pin "Y12") (pinfunction "PF10_Y12") (pintype "passive+no_connect"))
    )
    (net (code "165") (name "unconnected-(U1B-PF11-PadY10)") (class "Default")
      (node (ref "U1") (pin "Y10") (pinfunction "PF11_Y10") (pintype "passive+no_connect"))
    )
    (net (code "166") (name "unconnected-(U1B-PF12-PadY9)") (class "Default")
      (node (ref "U1") (pin "Y9") (pinfunction "PF12_Y9") (pintype "passive+no_connect"))
    )
    (net (code "167") (name "unconnected-(U1B-PF13-PadY5)") (class "Default")
      (node (ref "U1") (pin "Y5") (pinfunction "PF13_Y5") (pintype "passive+no_connect"))
    )
    (net (code "168") (name "unconnected-(U1B-PF14-PadAC4)") (class "Default")
      (node (ref "U1") (pin "AC4") (pinfunction "PF14_AC4") (pintype "passive+no_connect"))
    )
    (net (code "169") (name "unconnected-(U1B-PF15-PadY4)") (class "Default")
      (node (ref "U1") (pin "Y4") (pinfunction "PF15_Y4") (pintype "passive+no_connect"))
    )
    (net (code "170") (name "unconnected-(U1B-PG0-PadAC2)") (class "Default")
      (node (ref "U1") (pin "AC2") (pinfunction "PG0_AC2") (pintype "passive+no_connect"))
    )
    (net (code "171") (name "unconnected-(U1B-PG1-PadW1)") (class "Default")
      (node (ref "U1") (pin "W1") (pinfunction "PG1_W1") (pintype "passive+no_connect"))
    )
    (net (code "172") (name "unconnected-(U1B-PG2-PadV2)") (class "Default")
      (node (ref "U1") (pin "V2") (pinfunction "PG2_V2") (pintype "passive+no_connect"))
    )
    (net (code "173") (name "unconnected-(U1B-PG3-PadT4)") (class "Default")
      (node (ref "U1") (pin "T4") (pinfunction "PG3_T4") (pintype "passive+no_connect"))
    )
    (net (code "174") (name "unconnected-(U1B-PG4-PadAB2)") (class "Default")
      (node (ref "U1") (pin "AB2") (pinfunction "PG4_AB2") (pintype "passive+no_connect"))
    )
    (net (code "175") (name "unconnected-(U1B-PG5-PadY6)") (class "Default")
      (node (ref "U1") (pin "Y6") (pinfunction "PG5_Y6") (pintype "passive+no_connect"))
    )
    (net (code "176") (name "unconnected-(U1B-PG7-PadAC14)") (class "Default")
      (node (ref "U1") (pin "AC14") (pinfunction "PG7_AC14") (pintype "passive+no_connect"))
    )
    (net (code "177") (name "unconnected-(U1B-PG8-PadAB9)") (class "Default")
      (node (ref "U1") (pin "AB9") (pinfunction "PG8_AB9") (pintype "passive+no_connect"))
    )
    (net (code "178") (name "unconnected-(U1B-PG9-PadY13)") (class "Default")
      (node (ref "U1") (pin "Y13") (pinfunction "PG9_Y13") (pintype "passive+no_connect"))
    )
    (net (code "179") (name "unconnected-(U1B-PG10-PadAB11)") (class "Default")
      (node (ref "U1") (pin "AB11") (pinfunction "PG10_AB11") (pintype "passive+no_connect"))
    )
    (net (code "180") (name "unconnected-(U1B-PG11-PadY7)") (class "Default")
      (node (ref "U1") (pin "Y7") (pinfunction "PG11_Y7") (pintype "passive+no_connect"))
    )
    (net (code "181") (name "unconnected-(U1B-PG12-PadK4)") (class "Default")
      (node (ref "U1") (pin "K4") (pinfunction "PG12_K4") (pintype "passive+no_connect"))
    )
    (net (code "182") (name "unconnected-(U1B-PG13-PadAA2)") (class "Default")
      (node (ref "U1") (pin "AA2") (pinfunction "PG13_AA2") (pintype "passive+no_connect"))
    )
    (net (code "183") (name "unconnected-(U1B-PG14-PadAA1)") (class "Default")
      (node (ref "U1") (pin "AA1") (pinfunction "PG14_AA1") (pintype "passive+no_connect"))
    )
    (net (code "184") (name "unconnected-(U1B-PG15-PadB7)") (class "Default")
      (node (ref "U1") (pin "B7") (pinfunction "PG15_B7") (pintype "passive+no_connect"))
    )
    (net (code "185") (name "unconnected-(U1B-PH0-OSC_IN-PadP1)") (class "Default")
      (node (ref "U1") (pin "P1") (pinfunction "PH0-OSC_IN_P1") (pintype "passive+no_connect"))
    )
    (net (code "186") (name "unconnected-(U1B-PH1-OSC_OUT-PadP2)") (class "Default")
      (node (ref "U1") (pin "P2") (pinfunction "PH1-OSC_OUT_P2") (pintype "passive+no_connect"))
    )
    (net (code "187") (name "unconnected-(U1B-PH2-PadAB4)") (class "Default")
      (node (ref "U1") (pin "AB4") (pinfunction "PH2_AB4") (pintype "passive+no_connect"))
    )
    (net (code "188") (name "unconnected-(U1B-PH3-PadAA3)") (class "Default")
      (node (ref "U1") (pin "AA3") (pinfunction "PH3_AA3") (pintype "passive+no_connect"))
    )
    (net (code "189") (name "unconnected-(U1B-PH4-PadB3)") (class "Default")
      (node (ref "U1") (pin "B3") (pinfunction "PH4_B3") (pintype "passive+no_connect"))
    )
    (net (code "190") (name "unconnected-(U1B-PH5-PadA2)") (class "Default")
      (node (ref "U1") (pin "A2") (pinfunction "PH5_A2") (pintype "passive+no_connect"))
    )
    (net (code "191") (name "unconnected-(U1B-PH6-PadY11)") (class "Default")
      (node (ref "U1") (pin "Y11") (pinfunction "PH6_Y11") (pintype "passive+no_connect"))
    )
    (net (code "192") (name "unconnected-(U1B-PH7-PadW4)") (class "Default")
      (node (ref "U1") (pin "W4") (pinfunction "PH7_W4") (pintype "passive+no_connect"))
    )
    (net (code "193") (name "unconnected-(U1B-PH8-PadD5)") (class "Default")
      (node (ref "U1") (pin "D5") (pinfunction "PH8_D5") (pintype "passive+no_connect"))
    )
    (net (code "194") (name "unconnected-(U1B-PH9-PadC5)") (class "Default")
      (node (ref "U1") (pin "C5") (pinfunction "PH9_C5") (pintype "passive+no_connect"))
    )
    (net (code "195") (name "unconnected-(U1B-PH10-PadC2)") (class "Default")
      (node (ref "U1") (pin "C2") (pinfunction "PH10_C2") (pintype "passive+no_connect"))
    )
    (net (code "196") (name "unconnected-(U1B-PH11-PadC4)") (class "Default")
      (node (ref "U1") (pin "C4") (pinfunction "PH11_C4") (pintype "passive+no_connect"))
    )
    (net (code "197") (name "unconnected-(U1B-PH12-PadB2)") (class "Default")
      (node (ref "U1") (pin "B2") (pinfunction "PH12_B2") (pintype "passive+no_connect"))
    )
    (net (code "198") (name "unconnected-(U1B-PH13-PadD1)") (class "Default")
      (node (ref "U1") (pin "D1") (pinfunction "PH13_D1") (pintype "passive+no_connect"))
    )
    (net (code "199") (name "unconnected-(U1B-PH14-PadC3)") (class "Default")
      (node (ref "U1") (pin "C3") (pinfunction "PH14_C3") (pintype "passive+no_connect"))
    )
    (net (code "200") (name "unconnected-(U1B-PH15-PadB1)") (class "Default")
      (node (ref "U1") (pin "B1") (pinfunction "PH15_B1") (pintype "passive+no_connect"))
    )
    (net (code "201") (name "unconnected-(U1C-ANA0-PadU3)") (class "Default")
      (node (ref "U1") (pin "U3") (pinfunction "ANA0_U3") (pintype "passive+no_connect"))
    )
    (net (code "202") (name "unconnected-(U1C-ANA1-PadU4)") (class "Default")
      (node (ref "U1") (pin "U4") (pinfunction "ANA1_U4") (pintype "passive+no_connect"))
    )
    (net (code "203") (name "unconnected-(U1C-BOOT0-PadN1)") (class "Default")
      (node (ref "U1") (pin "N1") (pinfunction "BOOT0_N1") (pintype "passive+no_connect"))
    )
    (net (code "204") (name "unconnected-(U1C-BOOT1-PadN4)") (class "Default")
      (node (ref "U1") (pin "N4") (pinfunction "BOOT1_N4") (pintype "passive+no_connect"))
    )
    (net (code "205") (name "unconnected-(U1C-BOOT2-PadM2)") (class "Default")
      (node (ref "U1") (pin "M2") (pinfunction "BOOT2_M2") (pintype "passive+no_connect"))
    )
    (net (code "206") (name "unconnected-(U1C-DSI_CKN-PadA16)") (class "Default")
      (node (ref "U1") (pin "A16") (pinfunction "DSI_CKN_A16") (pintype "passive+no_connect"))
    )
    (net (code "207") (name "unconnected-(U1C-DSI_CKP-PadB16)") (class "Default")
      (node (ref "U1") (pin "B16") (pinfunction "DSI_CKP_B16") (pintype "passive+no_connect"))
    )
    (net (code "208") (name "unconnected-(U1C-DSI_D0N-PadB15)") (class "Default")
      (node (ref "U1") (pin "B15") (pinfunction "DSI_D0N_B15") (pintype "passive+no_connect"))
    )
    (net (code "209") (name "unconnected-(U1C-DSI_D0P-PadC15)") (class "Default")
      (node (ref "U1") (pin "C15") (pinfunction "DSI_D0P_C15") (pintype "passive+no_connect"))
    )
    (net (code "210") (name "unconnected-(U1C-DSI_D1N-PadA17)") (class "Default")
      (node (ref "U1") (pin "A17") (pinfunction "DSI_D1N_A17") (pintype "passive+no_connect"))
    )
    (net (code "211") (name "unconnected-(U1C-DSI_D1P-PadB17)") (class "Default")
      (node (ref "U1") (pin "B17") (pinfunction "DSI_D1P_B17") (pintype "passive+no_connect"))
    )
    (net (code "212") (name "unconnected-(U1C-NRST_CORE-PadM4)") (class "Default")
      (node (ref "U1") (pin "M4") (pinfunction "NRST_CORE_M4") (pintype "passive+no_connect"))
    )
    (net (code "213") (name "unconnected-(U1C-PDR_ON-PadR3)") (class "Default")
      (node (ref "U1") (pin "R3") (pinfunction "PDR_ON_R3") (pintype "passive+no_connect"))
    )
    (net (code "214") (name "unconnected-(U1C-PDR_ON_CORE-PadT3)") (class "Default")
      (node (ref "U1") (pin "T3") (pinfunction "PDR_ON_CORE_T3") (pintype "passive+no_connect"))
    )
    (net (code "215") (name "unconnected-(U1C-PI0-PadC1)") (class "Default")
      (node (ref "U1") (pin "C1") (pinfunction "PI0_C1") (pintype "passive+no_connect"))
    )
    (net (code "216") (name "unconnected-(U1C-PI1-PadE3)") (class "Default")
      (node (ref "U1") (pin "E3") (pinfunction "PI1_E3") (pintype "passive+no_connect"))
    )
    (net (code "217") (name "unconnected-(U1C-PI2-PadE2)") (class "Default")
      (node (ref "U1") (pin "E2") (pinfunction "PI2_E2") (pintype "passive+no_connect"))
    )
    (net (code "218") (name "unconnected-(U1C-PI3-PadE1)") (class "Default")
      (node (ref "U1") (pin "E1") (pinfunction "PI3_E1") (pintype "passive+no_connect"))
    )
    (net (code "219") (name "unconnected-(U1C-PI4-PadE4)") (class "Default")
      (node (ref "U1") (pin "E4") (pinfunction "PI4_E4") (pintype "passive+no_connect"))
    )
    (net (code "220") (name "unconnected-(U1C-PI5-PadF3)") (class "Default")
      (node (ref "U1") (pin "F3") (pinfunction "PI5_F3") (pintype "passive+no_connect"))
    )
    (net (code "221") (name "unconnected-(U1C-PI6-PadF4)") (class "Default")
      (node (ref "U1") (pin "F4") (pinfunction "PI6_F4") (pintype "passive+no_connect"))
    )
    (net (code "222") (name "unconnected-(U1C-PI7-PadF2)") (class "Default")
      (node (ref "U1") (pin "F2") (pinfunction "PI7_F2") (pintype "passive+no_connect"))
    )
    (net (code "223") (name "unconnected-(U1C-PI8-PadL4)") (class "Default")
      (node (ref "U1") (pin "L4") (pinfunction "PI8_L4") (pintype "passive+no_connect"))
    )
    (net (code "224") (name "unconnected-(U1C-PI9-PadH4)") (class "Default")
      (node (ref "U1") (pin "H4") (pinfunction "PI9_H4") (pintype "passive+no_connect"))
    )
    (net (code "225") (name "unconnected-(U1C-PI10-PadT1)") (class "Default")
      (node (ref "U1") (pin "T1") (pinfunction "PI10_T1") (pintype "passive+no_connect"))
    )
    (net (code "226") (name "unconnected-(U1C-PI11-PadP4)") (class "Default")
      (node (ref "U1") (pin "P4") (pinfunction "PI11_P4") (pintype "passive+no_connect"))
    )
    (net (code "227") (name "unconnected-(U1C-PWR_LP-PadN3)") (class "Default")
      (node (ref "U1") (pin "N3") (pinfunction "PWR_LP_N3") (pintype "passive+no_connect"))
    )
    (net (code "228") (name "unconnected-(U1C-PZ0-PadG3)") (class "Default")
      (node (ref "U1") (pin "G3") (pinfunction "PZ0_G3") (pintype "passive+no_connect"))
    )
    (net (code "229") (name "unconnected-(U1C-PZ1-PadG1)") (class "Default")
      (node (ref "U1") (pin "G1") (pinfunction "PZ1_G1") (pintype "passive+no_connect"))
    )
    (net (code "230") (name "unconnected-(U1C-PZ2-PadJ4)") (class "Default")
      (node (ref "U1") (pin "J4") (pinfunction "PZ2_J4") (pintype "passive+no_connect"))
    )
    (net (code "231") (name "unconnected-(U1C-PZ3-PadG4)") (class "Default")
      (node (ref "U1") (pin "G4") (pinfunction "PZ3_G4") (pintype "passive+no_connect"))
    )
    (net (code "232") (name "unconnected-(U1C-PZ4-PadG2)") (class "Default")
      (node (ref "U1") (pin "G2") (pinfunction "PZ4_G2") (pintype "passive+no_connect"))
    )
    (net (code "233") (name "unconnected-(U1C-PZ5-PadH2)") (class "Default")
      (node (ref "U1") (pin "H2") (pinfunction "PZ5_H2") (pintype "passive+no_connect"))
    )
    (net (code "234") (name "unconnected-(U1C-PZ6-PadH1)") (class "Default")
      (node (ref "U1") (pin "H1") (pinfunction "PZ6_H1") (pintype "passive+no_connect"))
    )
    (net (code "235") (name "unconnected-(U1C-PZ7-PadJ3)") (class "Default")
      (node (ref "U1") (pin "J3") (pinfunction "PZ7_J3") (pintype "passive+no_connect"))
    )
    (net (code "236") (name "unconnected-(U1E-DDR_A15-PadP20)") (class "Default")
      (node (ref "U1") (pin "P20") (pinfunction "DDR_A15_P20") (pintype "passive+no_connect"))
    )
    (net (code "237") (name "unconnected-(U1E-DDR_ATO-PadY19)") (class "Default")
      (node (ref "U1") (pin "Y19") (pinfunction "DDR_ATO_Y19") (pintype "passive+no_connect"))
    )
    (net (code "238") (name "unconnected-(U1E-DDR_DQ16-PadB22)") (class "Default")
      (node (ref "U1") (pin "B22") (pinfunction "DDR_DQ16_B22") (pintype "passive+no_connect"))
    )
    (net (code "239") (name "unconnected-(U1E-DDR_DQ17-PadD22)") (class "Default")
      (node (ref "U1") (pin "D22") (pinfunction "DDR_DQ17_D22") (pintype "passive+no_connect"))
    )
    (net (code "240") (name "unconnected-(U1E-DDR_DQ18-PadD23)") (class "Default")
      (node (ref "U1") (pin "D23") (pinfunction "DDR_DQ18_D23") (pintype "passive+no_connect"))
    )
    (net (code "241") (name "unconnected-(U1E-DDR_DQ19-PadB21)") (class "Default")
      (node (ref "U1") (pin "B21") (pinfunction "DDR_DQ19_B21") (pintype "passive+no_connect"))
    )
    (net (code "242") (name "unconnected-(U1E-DDR_DQ20-PadA21)") (class "Default")
      (node (ref "U1") (pin "A21") (pinfunction "DDR_DQ20_A21") (pintype "passive+no_connect"))
    )
    (net (code "243") (name "unconnected-(U1E-DDR_DQ21-PadE23)") (class "Default")
      (node (ref "U1") (pin "E23") (pinfunction "DDR_DQ21_E23") (pintype "passive+no_connect"))
    )
    (net (code "244") (name "unconnected-(U1E-DDR_DQ22-PadD21)") (class "Default")
      (node (ref "U1") (pin "D21") (pinfunction "DDR_DQ22_D21") (pintype "passive+no_connect"))
    )
    (net (code "245") (name "unconnected-(U1E-DDR_DQ23-PadA22)") (class "Default")
      (node (ref "U1") (pin "A22") (pinfunction "DDR_DQ23_A22") (pintype "passive+no_connect"))
    )
    (net (code "246") (name "unconnected-(U1E-DDR_DQ24-PadY23)") (class "Default")
      (node (ref "U1") (pin "Y23") (pinfunction "DDR_DQ24_Y23") (pintype "passive+no_connect"))
    )
    (net (code "247") (name "unconnected-(U1E-DDR_DQ25-PadY22)") (class "Default")
      (node (ref "U1") (pin "Y22") (pinfunction "DDR_DQ25_Y22") (pintype "passive+no_connect"))
    )
    (net (code "248") (name "unconnected-(U1E-DDR_DQ26-PadAB21)") (class "Default")
      (node (ref "U1") (pin "AB21") (pinfunction "DDR_DQ26_AB21") (pintype "passive+no_connect"))
    )
    (net (code "249") (name "unconnected-(U1E-DDR_DQ27-PadAB20)") (class "Default")
      (node (ref "U1") (pin "AB20") (pinfunction "DDR_DQ27_AB20") (pintype "passive+no_connect"))
    )
    (net (code "250") (name "unconnected-(U1E-DDR_DQ28-PadAC22)") (class "Default")
      (node (ref "U1") (pin "AC22") (pinfunction "DDR_DQ28_AC22") (pintype "passive+no_connect"))
    )
    (net (code "251") (name "unconnected-(U1E-DDR_DQ29-PadAC21)") (class "Default")
      (node (ref "U1") (pin "AC21") (pinfunction "DDR_DQ29_AC21") (pintype "passive+no_connect"))
    )
    (net (code "252") (name "unconnected-(U1E-DDR_DQ30-PadAA23)") (class "Default")
      (node (ref "U1") (pin "AA23") (pinfunction "DDR_DQ30_AA23") (pintype "passive+no_connect"))
    )
    (net (code "253") (name "unconnected-(U1E-DDR_DQ31-PadAA22)") (class "Default")
      (node (ref "U1") (pin "AA22") (pinfunction "DDR_DQ31_AA22") (pintype "passive+no_connect"))
    )
    (net (code "254") (name "unconnected-(U1E-DDR_DQM2-PadC23)") (class "Default")
      (node (ref "U1") (pin "C23") (pinfunction "DDR_DQM2_C23") (pintype "passive+no_connect"))
    )
    (net (code "255") (name "unconnected-(U1E-DDR_DQM3-PadAA20)") (class "Default")
      (node (ref "U1") (pin "AA20") (pinfunction "DDR_DQM3_AA20") (pintype "passive+no_connect"))
    )
    (net (code "256") (name "unconnected-(U1E-DDR_DQS2N-PadB23)") (class "Default")
      (node (ref "U1") (pin "B23") (pinfunction "DDR_DQS2N_B23") (pintype "passive+no_connect"))
    )
    (net (code "257") (name "unconnected-(U1E-DDR_DQS2P-PadC22)") (class "Default")
      (node (ref "U1") (pin "C22") (pinfunction "DDR_DQS2P_C22") (pintype "passive+no_connect"))
    )
    (net (code "258") (name "unconnected-(U1E-DDR_DQS3N-PadAB23)") (class "Default")
      (node (ref "U1") (pin "AB23") (pinfunction "DDR_DQS3N_AB23") (pintype "passive+no_connect"))
    )
    (net (code "259") (name "unconnected-(U1E-DDR_DQS3P-PadAB22)") (class "Default")
      (node (ref "U1") (pin "AB22") (pinfunction "DDR_DQS3P_AB22") (pintype "passive+no_connect"))
    )
    (net (code "260") (name "unconnected-(U1E-DDR_DTO0-PadK20)") (class "Default")
      (node (ref "U1") (pin "K20") (pinfunction "DDR_DTO0_K20") (pintype "passive+no_connect"))
    )
    (net (code "261") (name "unconnected-(U1E-DDR_DTO1-PadL21)") (class "Default")
      (node (ref "U1") (pin "L21") (pinfunction "DDR_DTO1_L21") (pintype "passive+no_connect"))
    )
  )
)
